# Battery_Control.net
KiCad netlist of a schematic drawn in EAGLE
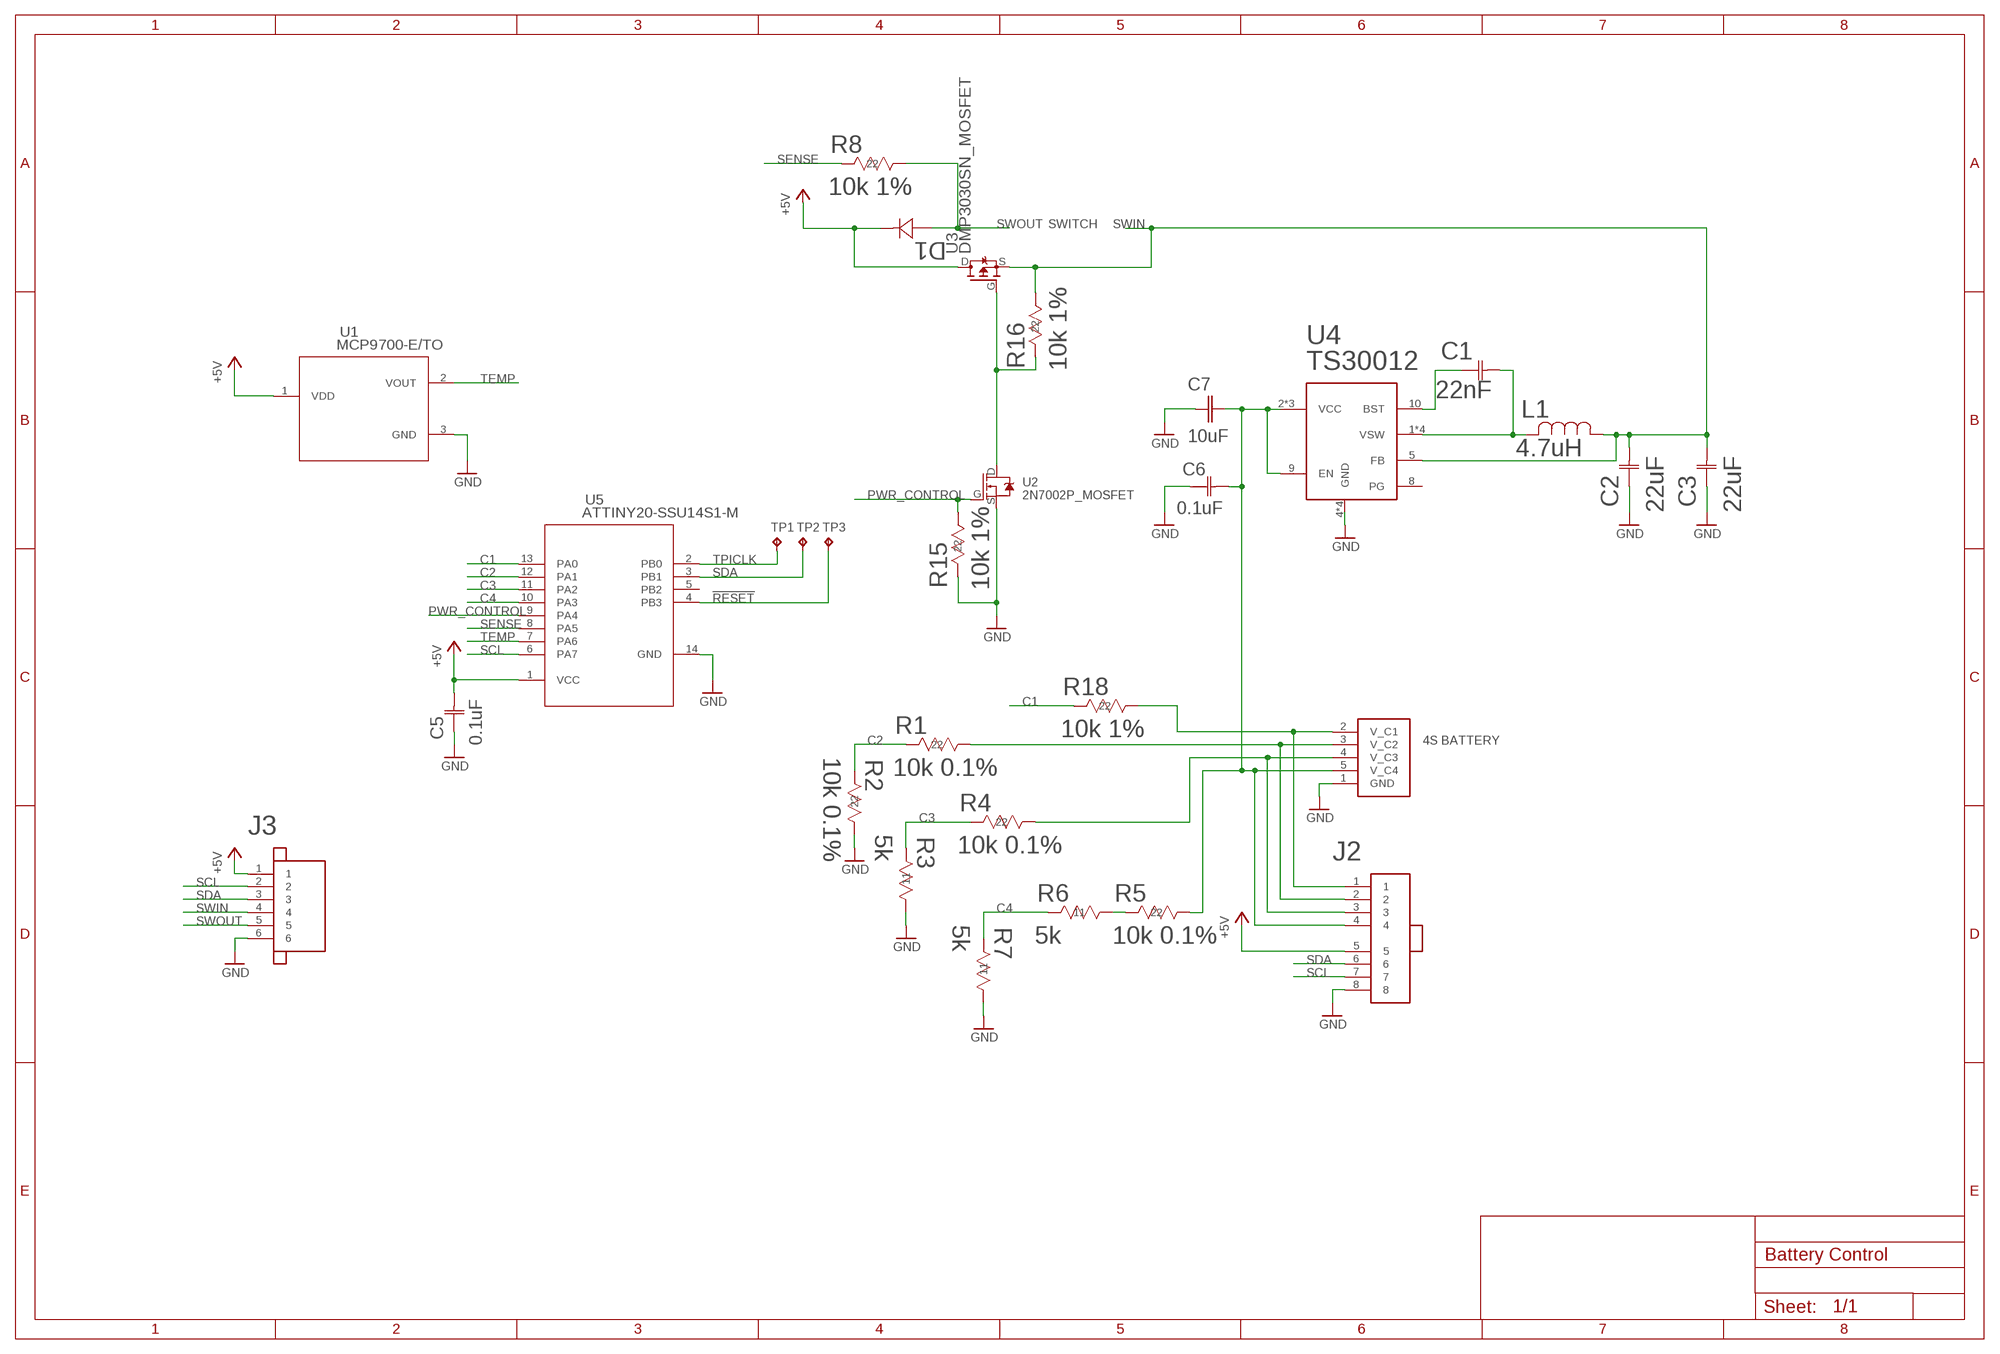
[diagram p0: schematic, sheet 1]

(export (version "E")
  (design (tool "Eeschema 10.0.6"))
  (components
    (comp (ref "C1")
      (value "22nF")
      (footprint "eagle-import:G-155-M")
      (fields (field (name "MANUFACTURER_PART_NUMBER") "GRM155R71H223KA12D"))
      (libsource (lib "eagle-import") (part "GRM155R71H223KA12DG-155-M"))
    )
    (comp (ref "C2")
      (value "22uF")
      (footprint "eagle-import:G-21")
      (fields
        (field (name "MANUFACTURER_PART_NUMBER") "GRM21BR60J226ME39L")
        (field (name "COPYRIGHT") "Copyright C 2015 Accelerated Designs. All rights reserved")
      )
      (libsource (lib "eagle-import") (part "GRM21BR60J226ME39L"))
    )
    (comp (ref "C3")
      (value "22uF")
      (footprint "eagle-import:G-21")
      (fields
        (field (name "MANUFACTURER_PART_NUMBER") "GRM21BR60J226ME39L")
        (field (name "COPYRIGHT") "Copyright C 2015 Accelerated Designs. All rights reserved")
      )
      (libsource (lib "eagle-import") (part "GRM21BR60J226ME39L"))
    )
    (comp (ref "C5")
      (value "0.1uF")
      (footprint "eagle-import:0805")
      (fields
        (field (name "MANUFACTURER_PART_NUMBER") "08055C104KAT2A")
        (field (name "COPYRIGHT") "Copyright C 2015 Accelerated Designs. All rights reserved")
      )
      (libsource (lib "eagle-import") (part "08055C104KAT2A"))
    )
    (comp (ref "C6")
      (value "0.1uF")
      (footprint "eagle-import:0805")
      (fields
        (field (name "MANUFACTURER_PART_NUMBER") "08055C104KAT2A")
        (field (name "COPYRIGHT") "Copyright C 2015 Accelerated Designs. All rights reserved")
      )
      (libsource (lib "eagle-import") (part "08055C104KAT2A"))
    )
    (comp (ref "C7")
      (value "10uF")
      (footprint "eagle-import:1206_MLCC")
      (libsource (lib "eagle-import") (part "10UF_CAPACITOR"))
    )
    (comp (ref "D1")
      (value "1N4148W-7-FSOD123-M")
      (footprint "eagle-import:SOD123-M")
      (fields
        (field (name "MANUFACTURER_PART_NUMBER") "1N4148W7F")
        (field (name "COPYRIGHT") "Copyright C 2015 Accelerated Designs. All rights reserved")
      )
      (libsource (lib "eagle-import") (part "1N4148W-7-FSOD123-M"))
    )
    (comp (ref "J1")
      (value "JST-XH_5POS")
      (footprint "eagle-import:JST-XH_5POS")
      (libsource (lib "eagle-import") (part "JST-XH_5POS"))
    )
    (comp (ref "J2")
      (value "SPRING_BTB_8POS_FEMALE")
      (footprint "eagle-import:SPRING_BTB_8POS_FEMALE")
      (libsource (lib "eagle-import") (part "SPRING_BTB_8POS_FEMALE"))
    )
    (comp (ref "J3")
      (value "JST_SH_6POS_SIDE")
      (footprint "eagle-import:JST_SH_6POS_SIDE")
      (libsource (lib "eagle-import") (part "JST_SH_6POS_SIDE"))
    )
    (comp (ref "L1")
      (value "4.7uH")
      (footprint "eagle-import:1008")
      (libsource (lib "eagle-import") (part "DFE252012P-4R7M=P2{dblquote}"))
    )
    (comp (ref "R1")
      (value "10k 0.1%")
      (footprint "eagle-import:RC0805N")
      (fields
        (field (name "DIGIKEYPARTNUMBER") "P10KDATRND")
        (field (name "MANUFACTURER_PART_NUMBER") "ERA6AEB103V")
        (field (name "TOLERANCE") "0.1%")
        (field (name "COPYRIGHT") "Copyright C 2015 Accelerated Designs. All rights reserved")
      )
      (libsource (lib "eagle-import") (part "ERA-6AEB103V"))
    )
    (comp (ref "R2")
      (value "10k 0.1%")
      (footprint "eagle-import:RC0805N")
      (fields
        (field (name "DIGIKEYPARTNUMBER") "P10KDATRND")
        (field (name "MANUFACTURER_PART_NUMBER") "ERA6AEB103V")
        (field (name "TOLERANCE") "0.1%")
        (field (name "COPYRIGHT") "Copyright C 2015 Accelerated Designs. All rights reserved")
      )
      (libsource (lib "eagle-import") (part "ERA-6AEB103V"))
    )
    (comp (ref "R3")
      (value "5k")
      (footprint "eagle-import:0402")
      (fields
        (field (name "MANUFACTURER_PART_NUMBER") "PNM0402E5001BST1")
        (field (name "COPYRIGHT") "Copyright C 2015 Accelerated Designs. All rights reserved")
      )
      (libsource (lib "eagle-import") (part "PNM0402E5001BST1"))
    )
    (comp (ref "R4")
      (value "10k 0.1%")
      (footprint "eagle-import:RC0805N")
      (fields
        (field (name "DIGIKEYPARTNUMBER") "P10KDATRND")
        (field (name "MANUFACTURER_PART_NUMBER") "ERA6AEB103V")
        (field (name "TOLERANCE") "0.1%")
        (field (name "COPYRIGHT") "Copyright C 2015 Accelerated Designs. All rights reserved")
      )
      (libsource (lib "eagle-import") (part "ERA-6AEB103V"))
    )
    (comp (ref "R5")
      (value "10k 0.1%")
      (footprint "eagle-import:RC0805N")
      (fields
        (field (name "DIGIKEYPARTNUMBER") "P10KDATRND")
        (field (name "MANUFACTURER_PART_NUMBER") "ERA6AEB103V")
        (field (name "TOLERANCE") "0.1%")
        (field (name "COPYRIGHT") "Copyright C 2015 Accelerated Designs. All rights reserved")
      )
      (libsource (lib "eagle-import") (part "ERA-6AEB103V"))
    )
    (comp (ref "R6")
      (value "5k")
      (footprint "eagle-import:0402")
      (fields
        (field (name "MANUFACTURER_PART_NUMBER") "PNM0402E5001BST1")
        (field (name "COPYRIGHT") "Copyright C 2015 Accelerated Designs. All rights reserved")
      )
      (libsource (lib "eagle-import") (part "PNM0402E5001BST1"))
    )
    (comp (ref "R7")
      (value "5k")
      (footprint "eagle-import:0402")
      (fields
        (field (name "MANUFACTURER_PART_NUMBER") "PNM0402E5001BST1")
        (field (name "COPYRIGHT") "Copyright C 2015 Accelerated Designs. All rights reserved")
      )
      (libsource (lib "eagle-import") (part "PNM0402E5001BST1"))
    )
    (comp (ref "R8")
      (value "10k 1%")
      (footprint "eagle-import:RC0805N")
      (fields
        (field (name "DIGIKEYPARTNUMBER") "P10KDATRND")
        (field (name "MANUFACTURER_PART_NUMBER") "ERA6AEB103V")
        (field (name "TOLERANCE") "0.1%")
        (field (name "COPYRIGHT") "Copyright C 2015 Accelerated Designs. All rights reserved")
      )
      (libsource (lib "eagle-import") (part "ERA-6AEB103V"))
    )
    (comp (ref "R15")
      (value "10k 1%")
      (footprint "eagle-import:RC0805N")
      (fields
        (field (name "DIGIKEYPARTNUMBER") "P10KDATRND")
        (field (name "MANUFACTURER_PART_NUMBER") "ERA6AEB103V")
        (field (name "TOLERANCE") "0.1%")
        (field (name "COPYRIGHT") "Copyright C 2015 Accelerated Designs. All rights reserved")
      )
      (libsource (lib "eagle-import") (part "ERA-6AEB103V"))
    )
    (comp (ref "R16")
      (value "10k 1%")
      (footprint "eagle-import:RC0805N")
      (fields
        (field (name "DIGIKEYPARTNUMBER") "P10KDATRND")
        (field (name "MANUFACTURER_PART_NUMBER") "ERA6AEB103V")
        (field (name "TOLERANCE") "0.1%")
        (field (name "COPYRIGHT") "Copyright C 2015 Accelerated Designs. All rights reserved")
      )
      (libsource (lib "eagle-import") (part "ERA-6AEB103V"))
    )
    (comp (ref "R18")
      (value "10k 1%")
      (footprint "eagle-import:RC0805N")
      (fields
        (field (name "DIGIKEYPARTNUMBER") "P10KDATRND")
        (field (name "MANUFACTURER_PART_NUMBER") "ERA6AEB103V")
        (field (name "TOLERANCE") "0.1%")
        (field (name "COPYRIGHT") "Copyright C 2015 Accelerated Designs. All rights reserved")
      )
      (libsource (lib "eagle-import") (part "ERA-6AEB103V"))
    )
    (comp (ref "TP1")
      (value "TPB2,54")
      (footprint "eagle-import:B2,54")
      (libsource (lib "eagle-import") (part "TPB2,54"))
    )
    (comp (ref "TP2")
      (value "TPB2,54")
      (footprint "eagle-import:B2,54")
      (libsource (lib "eagle-import") (part "TPB2,54"))
    )
    (comp (ref "TP3")
      (value "TPB2,54")
      (footprint "eagle-import:B2,54")
      (libsource (lib "eagle-import") (part "TPB2,54"))
    )
    (comp (ref "U1")
      (value "MCP9700-E/TO")
      (footprint "eagle-import:TO-92_MC")
      (fields (field (name "MANUFACTURER_PART_NUMBER") "MCP9700ETO"))
      (libsource (lib "eagle-import") (part "MCP9700-E/TO"))
    )
    (comp (ref "U2")
      (value "2N7002P_MOSFET")
      (footprint "eagle-import:SOT-23_(TO-236AB)")
      (libsource (lib "eagle-import") (part "2N7002P_MOSFET"))
    )
    (comp (ref "U3")
      (value "DMP3030SN_MOSFET")
      (footprint "eagle-import:SC59_MOSFET")
      (libsource (lib "eagle-import") (part "DMP3030SN_MOSFET"))
    )
    (comp (ref "U4")
      (value "TS30012")
      (footprint "eagle-import:16-VQFN")
      (libsource (lib "eagle-import") (part "TS30012"))
    )
    (comp (ref "U5")
      (value "ATTINY20-SSU14S1-M")
      (footprint "eagle-import:14S1-M")
      (fields (field (name "MANUFACTURER_PART_NUMBER") "ATTINY20SSU"))
      (libsource (lib "eagle-import") (part "ATTINY20-SSU14S1-M"))
    )
  )
  (nets
    (net (code "1") (name "+5V") (class "Default")
      (node (ref "C5") (pin "2") (pinfunction "2_2") (pintype "passive"))
      (node (ref "D1") (pin "C") (pinfunction "12_C") (pintype "passive"))
      (node (ref "J2") (pin "5") (pinfunction "5_5") (pintype "bidirectional"))
      (node (ref "J3") (pin "1") (pinfunction "1_1") (pintype "bidirectional"))
      (node (ref "U1") (pin "1") (pinfunction "VDD_1") (pintype "passive"))
      (node (ref "U3") (pin "D") (pinfunction "D_D") (pintype "passive"))
      (node (ref "U5") (pin "1") (pinfunction "VCC_1") (pintype "passive"))
    )
    (net (code "2") (name "/C1") (class "Default")
      (node (ref "R18") (pin "2") (pinfunction "22_2") (pintype "passive"))
      (node (ref "U5") (pin "13") (pinfunction "PA0_13") (pintype "passive"))
    )
    (net (code "3") (name "/C2") (class "Default")
      (node (ref "R1") (pin "2") (pinfunction "22_2") (pintype "passive"))
      (node (ref "R2") (pin "2") (pinfunction "22_2") (pintype "passive"))
      (node (ref "U5") (pin "12") (pinfunction "PA1_12") (pintype "passive"))
    )
    (net (code "4") (name "/C3") (class "Default")
      (node (ref "R3") (pin "1") (pinfunction "11_1") (pintype "passive"))
      (node (ref "R4") (pin "2") (pinfunction "22_2") (pintype "passive"))
      (node (ref "U5") (pin "11") (pinfunction "PA2_11") (pintype "passive"))
    )
    (net (code "5") (name "/C4") (class "Default")
      (node (ref "R6") (pin "1") (pinfunction "11_1") (pintype "passive"))
      (node (ref "R7") (pin "1") (pinfunction "11_1") (pintype "passive"))
      (node (ref "U5") (pin "10") (pinfunction "PA3_10") (pintype "passive"))
    )
    (net (code "6") (name "/PWR_CONTROL") (class "Default")
      (node (ref "R15") (pin "1") (pinfunction "11_1") (pintype "passive"))
      (node (ref "U2") (pin "G") (pinfunction "G_G") (pintype "passive"))
      (node (ref "U5") (pin "9") (pinfunction "PA4_9") (pintype "passive"))
    )
    (net (code "7") (name "/SCL") (class "Default")
      (node (ref "J2") (pin "7") (pinfunction "7_7") (pintype "bidirectional"))
      (node (ref "J3") (pin "2") (pinfunction "2_2") (pintype "bidirectional"))
      (node (ref "U5") (pin "6") (pinfunction "PA7_6") (pintype "passive"))
    )
    (net (code "8") (name "/SDA") (class "Default")
      (node (ref "J2") (pin "6") (pinfunction "6_6") (pintype "bidirectional"))
      (node (ref "J3") (pin "3") (pinfunction "3_3") (pintype "bidirectional"))
      (node (ref "TP2") (pin "TP") (pinfunction "TP_TP") (pintype "input"))
      (node (ref "U5") (pin "3") (pinfunction "PB1_3") (pintype "passive"))
    )
    (net (code "9") (name "/SENSE") (class "Default")
      (node (ref "R8") (pin "2") (pinfunction "22_2") (pintype "passive"))
      (node (ref "U5") (pin "8") (pinfunction "PA5_8") (pintype "passive"))
    )
    (net (code "10") (name "/SWIN") (class "Default")
      (node (ref "C2") (pin "2") (pinfunction "22_2") (pintype "passive"))
      (node (ref "C3") (pin "2") (pinfunction "22_2") (pintype "passive"))
      (node (ref "J3") (pin "4") (pinfunction "4_4") (pintype "bidirectional"))
      (node (ref "L1") (pin "P$1") (pinfunction "1_P$1") (pintype "passive"))
      (node (ref "R16") (pin "1") (pinfunction "11_1") (pintype "passive"))
      (node (ref "U3") (pin "S") (pinfunction "S_S") (pintype "passive"))
      (node (ref "U4") (pin "5") (pinfunction "FB_5") (pintype "bidirectional"))
    )
    (net (code "11") (name "/SWOUT") (class "Default")
      (node (ref "D1") (pin "A") (pinfunction "21_A") (pintype "passive"))
      (node (ref "J3") (pin "5") (pinfunction "5_5") (pintype "bidirectional"))
      (node (ref "R8") (pin "1") (pinfunction "11_1") (pintype "passive"))
    )
    (net (code "12") (name "/TEMP") (class "Default")
      (node (ref "U1") (pin "2") (pinfunction "VOUT_2") (pintype "passive"))
      (node (ref "U5") (pin "7") (pinfunction "PA6_7") (pintype "passive"))
    )
    (net (code "13") (name "/TPICLK") (class "Default")
      (node (ref "TP1") (pin "TP") (pinfunction "TP_TP") (pintype "input"))
      (node (ref "U5") (pin "2") (pinfunction "PB0_2") (pintype "passive"))
    )
    (net (code "14") (name "/~{RESET}") (class "Default")
      (node (ref "TP3") (pin "TP") (pinfunction "TP_TP") (pintype "input"))
      (node (ref "U5") (pin "4") (pinfunction "PB3_4") (pintype "passive"))
    )
    (net (code "15") (name "GND") (class "Default")
      (node (ref "C2") (pin "1") (pinfunction "11_1") (pintype "passive"))
      (node (ref "C3") (pin "1") (pinfunction "11_1") (pintype "passive"))
      (node (ref "C5") (pin "1") (pinfunction "1_1") (pintype "passive"))
      (node (ref "C6") (pin "1") (pinfunction "1_1") (pintype "passive"))
      (node (ref "C7") (pin "P$1") (pinfunction "1_P$1") (pintype "bidirectional"))
      (node (ref "J1") (pin "1") (pinfunction "GND_1") (pintype "power_in"))
      (node (ref "J2") (pin "8") (pinfunction "8_8") (pintype "bidirectional"))
      (node (ref "J3") (pin "6") (pinfunction "6_6") (pintype "bidirectional"))
      (node (ref "R15") (pin "2") (pinfunction "22_2") (pintype "passive"))
      (node (ref "R2") (pin "1") (pinfunction "11_1") (pintype "passive"))
      (node (ref "R3") (pin "2") (pinfunction "22_2") (pintype "passive"))
      (node (ref "R7") (pin "2") (pinfunction "22_2") (pintype "passive"))
      (node (ref "U1") (pin "3") (pinfunction "GND_3") (pintype "passive"))
      (node (ref "U2") (pin "S") (pinfunction "S_S") (pintype "passive"))
      (node (ref "U4") (pin "14") (pinfunction "GND_14") (pintype "bidirectional"))
      (node (ref "U4") (pin "15") (pinfunction "GND_15") (pintype "bidirectional"))
      (node (ref "U4") (pin "17") (pinfunction "GND_17") (pintype "bidirectional"))
      (node (ref "U4") (pin "4") (pinfunction "GND_4") (pintype "bidirectional"))
      (node (ref "U5") (pin "14") (pinfunction "GND_14") (pintype "passive"))
    )
    (net (code "16") (name "Net-(C1-11)") (class "Default")
      (node (ref "C1") (pin "1") (pinfunction "11_1") (pintype "passive"))
      (node (ref "U4") (pin "10") (pinfunction "BST_10") (pintype "bidirectional"))
    )
    (net (code "17") (name "Net-(C1-22)") (class "Default")
      (node (ref "C1") (pin "2") (pinfunction "22_2") (pintype "passive"))
      (node (ref "L1") (pin "P$2") (pinfunction "2_P$2") (pintype "passive"))
      (node (ref "U4") (pin "1") (pinfunction "VSW_1") (pintype "bidirectional"))
      (node (ref "U4") (pin "12") (pinfunction "VSW_12") (pintype "bidirectional"))
      (node (ref "U4") (pin "13") (pinfunction "VSW_13") (pintype "bidirectional"))
      (node (ref "U4") (pin "16") (pinfunction "VSW_16") (pintype "bidirectional"))
    )
    (net (code "18") (name "Net-(C7-2)") (class "Default")
      (node (ref "C6") (pin "2") (pinfunction "2_2") (pintype "passive"))
      (node (ref "C7") (pin "P$2") (pinfunction "2_P$2") (pintype "bidirectional"))
      (node (ref "J1") (pin "5") (pinfunction "V_C4_5") (pintype "bidirectional"))
      (node (ref "J2") (pin "4") (pinfunction "4_4") (pintype "bidirectional"))
      (node (ref "R5") (pin "1") (pinfunction "11_1") (pintype "passive"))
      (node (ref "U4") (pin "11") (pinfunction "VCC_11") (pintype "bidirectional"))
      (node (ref "U4") (pin "2") (pinfunction "VCC_2") (pintype "bidirectional"))
      (node (ref "U4") (pin "3") (pinfunction "VCC_3") (pintype "bidirectional"))
      (node (ref "U4") (pin "9") (pinfunction "EN_9") (pintype "bidirectional"))
    )
    (net (code "19") (name "Net-(J1-V_C1)") (class "Default")
      (node (ref "J1") (pin "2") (pinfunction "V_C1_2") (pintype "bidirectional"))
      (node (ref "J2") (pin "1") (pinfunction "1_1") (pintype "bidirectional"))
      (node (ref "R18") (pin "1") (pinfunction "11_1") (pintype "passive"))
    )
    (net (code "20") (name "Net-(J1-V_C2)") (class "Default")
      (node (ref "J1") (pin "3") (pinfunction "V_C2_3") (pintype "bidirectional"))
      (node (ref "J2") (pin "2") (pinfunction "2_2") (pintype "bidirectional"))
      (node (ref "R1") (pin "1") (pinfunction "11_1") (pintype "passive"))
    )
    (net (code "21") (name "Net-(J1-V_C3)") (class "Default")
      (node (ref "J1") (pin "4") (pinfunction "V_C3_4") (pintype "bidirectional"))
      (node (ref "J2") (pin "3") (pinfunction "3_3") (pintype "bidirectional"))
      (node (ref "R4") (pin "1") (pinfunction "11_1") (pintype "passive"))
    )
    (net (code "22") (name "Net-(R5-22)") (class "Default")
      (node (ref "R5") (pin "2") (pinfunction "22_2") (pintype "passive"))
      (node (ref "R6") (pin "2") (pinfunction "22_2") (pintype "passive"))
    )
    (net (code "23") (name "Net-(R16-22)") (class "Default")
      (node (ref "R16") (pin "2") (pinfunction "22_2") (pintype "passive"))
      (node (ref "U2") (pin "D") (pinfunction "D_D") (pintype "passive"))
      (node (ref "U3") (pin "G") (pinfunction "G_G") (pintype "passive"))
    )
    (net (code "24") (name "unconnected-(U4-PG-Pad8)") (class "Default")
      (node (ref "U4") (pin "8") (pinfunction "PG_8") (pintype "bidirectional"))
    )
    (net (code "25") (name "unconnected-(U5-PB2-Pad5)") (class "Default")
      (node (ref "U5") (pin "5") (pinfunction "PB2_5") (pintype "passive"))
    )
  )
)
